# Motor_Controller_removable_maintenance_a.net
KiCad netlist of a schematic drawn in EAGLE
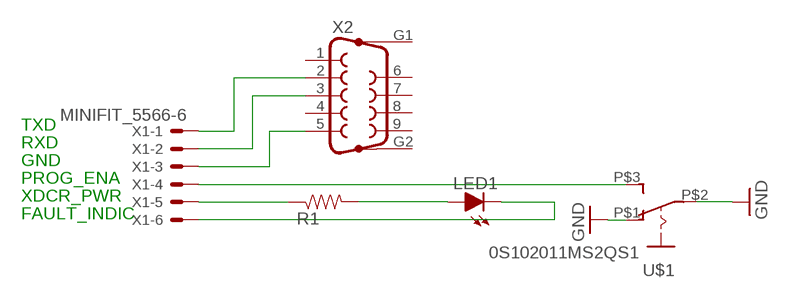
[diagram p0: schematic, sheet 1]

(export (version "E")
  (design (tool "Eeschema 10.0.6"))
  (components
    (comp (ref "LED1")
      (value "LED-0805")
      (footprint "eagle-import:LED-805")
      (libsource (lib "eagle-import") (part "LED-0805"))
    )
    (comp (ref "R1")
      (value "RESISTOR0805-RES")
      (footprint "eagle-import:0805")
      (libsource (lib "eagle-import") (part "RESISTOR0805-RES"))
    )
    (comp (ref "U$1")
      (value "0S102011MS2QS1")
      (footprint "eagle-import:0S102011MS2QS1")
      (libsource (lib "eagle-import") (part "0S102011MS2QS1"))
    )
    (comp (ref "X1")
      (value "MINIFIT_5566-6")
      (footprint "eagle-import:MINIFIT_5566-6")
      (fields (field (name "MPN") "95566-61002"))
      (libsource (lib "eagle-import") (part "MINIFIT_5566-6"))
    )
    (comp (ref "X2")
      (value "F09HP")
      (footprint "eagle-import:F09HP")
      (libsource (lib "eagle-import") (part "F09HP"))
    )
  )
  (nets
    (net (code "1") (name "GND") (class "Default")
      (node (ref "U$1") (pin "P$1") (pinfunction "O_P$1") (pintype "passive"))
      (node (ref "U$1") (pin "P$2") (pinfunction "P_P$2") (pintype "passive"))
    )
    (net (code "2") (name "Net-(LED1-PadA)") (class "Default")
      (node (ref "LED1") (pin "A") (pinfunction "A_A") (pintype "passive"))
      (node (ref "R1") (pin "2") (pinfunction "2_2") (pintype "passive"))
    )
    (net (code "3") (name "Net-(U$1-S)") (class "Default")
      (node (ref "U$1") (pin "P$3") (pinfunction "S_P$3") (pintype "passive"))
      (node (ref "X1") (pin "4") (pinfunction "S_4") (pintype "passive"))
    )
    (net (code "4") (name "Net-(X1A-S)") (class "Default")
      (node (ref "X1") (pin "1") (pinfunction "S_1") (pintype "passive"))
      (node (ref "X2") (pin "2") (pinfunction "2_2") (pintype "passive"))
    )
    (net (code "5") (name "Net-(X1B-S)") (class "Default")
      (node (ref "X1") (pin "2") (pinfunction "S_2") (pintype "passive"))
      (node (ref "X2") (pin "3") (pinfunction "3_3") (pintype "passive"))
    )
    (net (code "6") (name "Net-(X1C-S)") (class "Default")
      (node (ref "X1") (pin "3") (pinfunction "S_3") (pintype "passive"))
      (node (ref "X2") (pin "5") (pinfunction "5_5") (pintype "passive"))
    )
    (net (code "7") (name "Net-(X1E-S)") (class "Default")
      (node (ref "R1") (pin "1") (pinfunction "1_1") (pintype "passive"))
      (node (ref "X1") (pin "5") (pinfunction "S_5") (pintype "passive"))
    )
    (net (code "8") (name "Net-(X1F-S)") (class "Default")
      (node (ref "LED1") (pin "C") (pinfunction "C_C") (pintype "passive"))
      (node (ref "X1") (pin "6") (pinfunction "S_6") (pintype "passive"))
    )
    (net (code "9") (name "unconnected-(X2-Pad1)") (class "Default")
      (node (ref "X2") (pin "1") (pinfunction "1_1") (pintype "passive"))
    )
    (net (code "10") (name "unconnected-(X2-Pad4)") (class "Default")
      (node (ref "X2") (pin "4") (pinfunction "4_4") (pintype "passive"))
    )
    (net (code "11") (name "unconnected-(X2-Pad6)") (class "Default")
      (node (ref "X2") (pin "6") (pinfunction "6_6") (pintype "passive"))
    )
    (net (code "12") (name "unconnected-(X2-Pad7)") (class "Default")
      (node (ref "X2") (pin "7") (pinfunction "7_7") (pintype "passive"))
    )
    (net (code "13") (name "unconnected-(X2-Pad8)") (class "Default")
      (node (ref "X2") (pin "8") (pinfunction "8_8") (pintype "passive"))
    )
    (net (code "14") (name "unconnected-(X2-Pad9)") (class "Default")
      (node (ref "X2") (pin "9") (pinfunction "9_9") (pintype "passive"))
    )
    (net (code "15") (name "unconnected-(X2-PadG1)") (class "Default")
      (node (ref "X2") (pin "G1") (pinfunction "G1_G1") (pintype "passive"))
    )
    (net (code "16") (name "unconnected-(X2-PadG2)") (class "Default")
      (node (ref "X2") (pin "G2") (pinfunction "G2_G2") (pintype "passive"))
    )
  )
)
